# LKS_074DO.net
KiCad netlist of a schematic drawn in Altium Designer
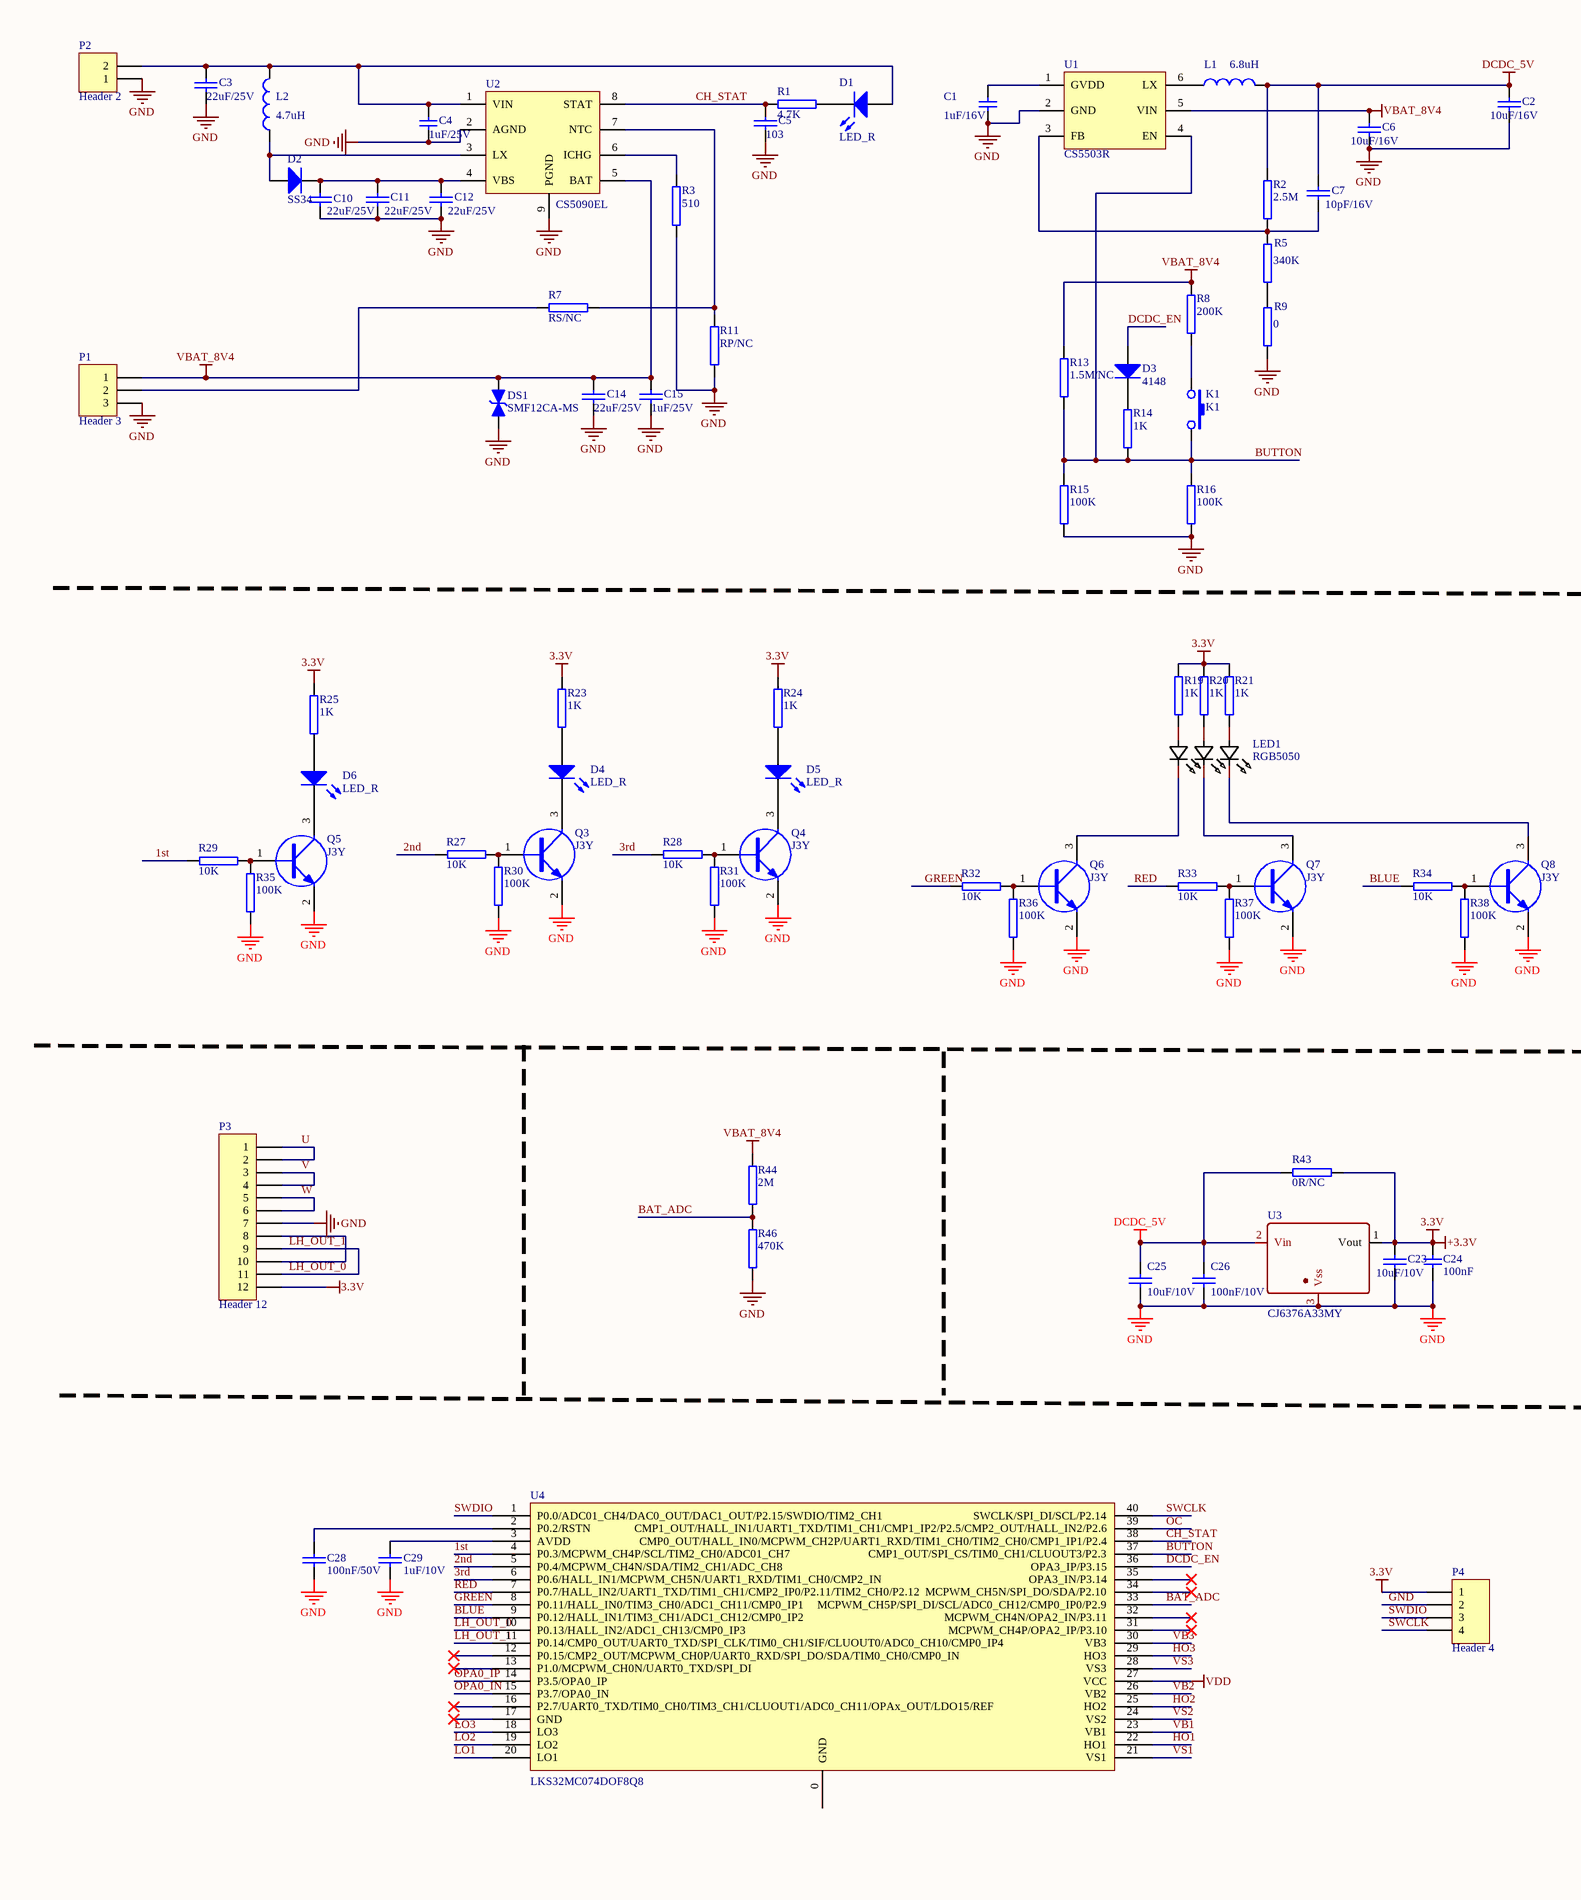
[diagram p0: LKS_074DO.SchDoc, left]
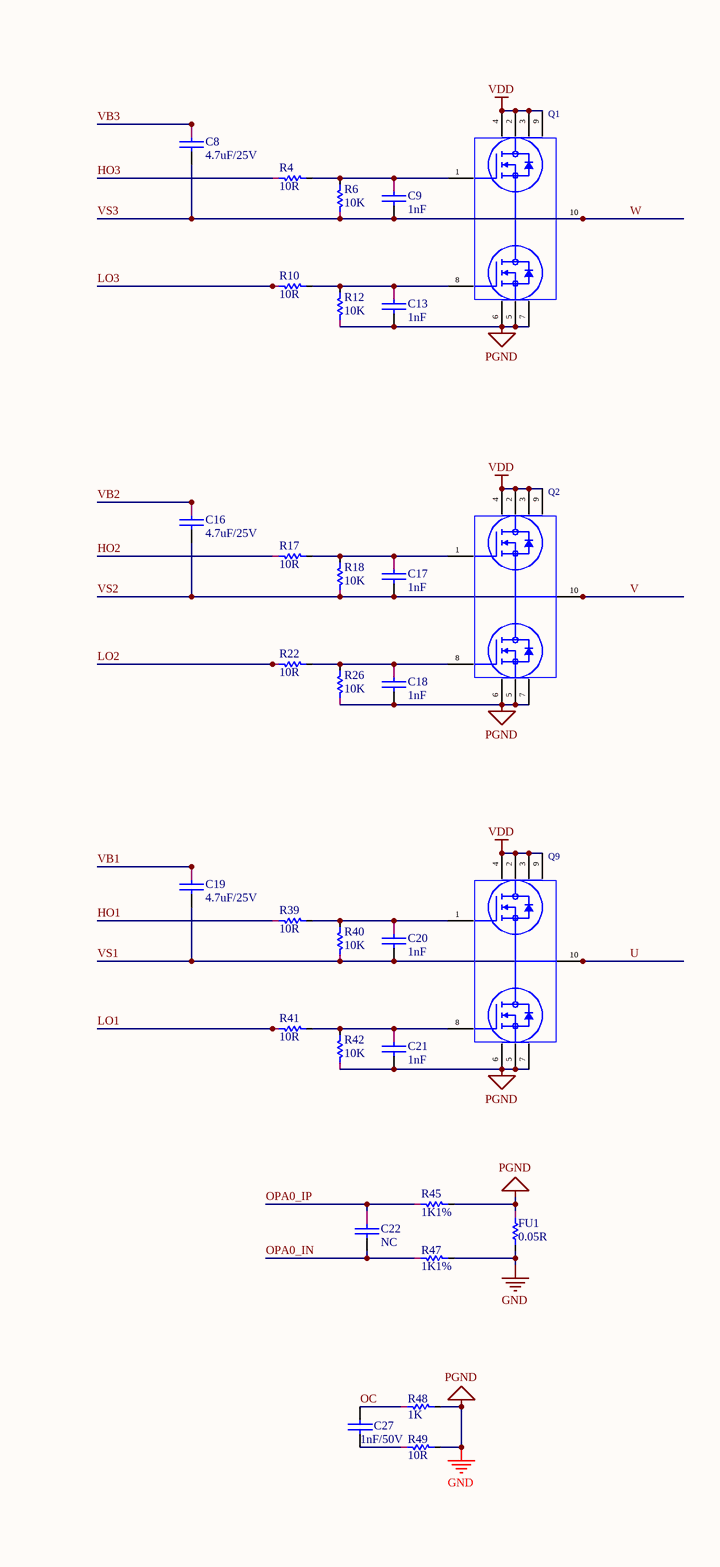
[diagram p1: LKS_074DO.SchDoc, right]

(export (version "E")
  (design (tool "Eeschema 10.0.6"))
  (components
    (comp (ref "C1") (value "1uF/16V") (footprint "C 0402_M") (libsource (lib "") (part "CAP_2")))
    (comp (ref "C2")
      (value "10uF/16V")
      (footprint "0805C")
      (description "Capacitor")
      (libsource (lib "*") (part "CAP"))
    )
    (comp (ref "C3")
      (value "22uF/25V")
      (footprint "0805C")
      (description "Capacitor")
      (libsource (lib "*") (part "CAP"))
    )
    (comp (ref "C4") (value "1uF/25V") (footprint "C 0402_M") (libsource (lib "") (part "CAP_2")))
    (comp (ref "C5")
      (value "103")
      (footprint "R 0402_M")
      (description "Capacitor")
      (libsource (lib "*") (part "CAP"))
    )
    (comp (ref "C6")
      (value "10uF/16V")
      (footprint "0805C")
      (description "Capacitor")
      (libsource (lib "*") (part "CAP"))
    )
    (comp (ref "C7")
      (value "10pF/16V")
      (footprint "C 0402_M")
      (description "Capacitor")
      (libsource (lib "*") (part "CAP"))
    )
    (comp (ref "C8")
      (value "4.7uF/25V")
      (footprint "C 0603_M")
      (description "Capacitor")
      (libsource (lib "") (part "CAP_1"))
    )
    (comp (ref "C9")
      (value "1nF")
      (footprint "C 0402_M")
      (description "Capacitor")
      (libsource (lib "") (part "CAP_1"))
    )
    (comp (ref "C10")
      (value "22uF/25V")
      (footprint "0805C")
      (description "Capacitor")
      (libsource (lib "*") (part "CAP"))
    )
    (comp (ref "C11")
      (value "22uF/25V")
      (footprint "0805C")
      (description "Capacitor")
      (libsource (lib "*") (part "CAP"))
    )
    (comp (ref "C12")
      (value "22uF/25V")
      (footprint "0805C")
      (description "Capacitor")
      (libsource (lib "*") (part "CAP"))
    )
    (comp (ref "C13")
      (value "1nF")
      (footprint "C 0402_M")
      (description "Capacitor")
      (libsource (lib "") (part "CAP_1"))
    )
    (comp (ref "C14")
      (value "22uF/25V")
      (footprint "0805C")
      (description "Capacitor")
      (libsource (lib "*") (part "CAP"))
    )
    (comp (ref "C15")
      (value "1uF/25V")
      (footprint "C 0603_M")
      (description "Capacitor")
      (libsource (lib "*") (part "CAP"))
    )
    (comp (ref "C16")
      (value "4.7uF/25V")
      (footprint "C 0603_M")
      (description "Capacitor")
      (libsource (lib "") (part "CAP_1"))
    )
    (comp (ref "C17")
      (value "1nF")
      (footprint "C 0402_M")
      (description "Capacitor")
      (libsource (lib "") (part "CAP_1"))
    )
    (comp (ref "C18")
      (value "1nF")
      (footprint "C 0402_M")
      (description "Capacitor")
      (libsource (lib "") (part "CAP_1"))
    )
    (comp (ref "C19")
      (value "4.7uF/25V")
      (footprint "C 0603_M")
      (description "Capacitor")
      (libsource (lib "") (part "CAP_1"))
    )
    (comp (ref "C20")
      (value "1nF")
      (footprint "C 0402_M")
      (description "Capacitor")
      (libsource (lib "") (part "CAP_1"))
    )
    (comp (ref "C21")
      (value "1nF")
      (footprint "C 0402_M")
      (description "Capacitor")
      (libsource (lib "") (part "CAP_1"))
    )
    (comp (ref "C22")
      (value "NC")
      (footprint "C 0402_M")
      (description "Capacitor")
      (libsource (lib "") (part "CAP_1"))
    )
    (comp (ref "C23")
      (value "10uF/10V")
      (footprint "0805C")
      (description "Capacitor")
      (libsource (lib "*") (part "CAP"))
    )
    (comp (ref "C24") (value "100nF") (footprint "C 0402_M") (libsource (lib "") (part "CAP_2")))
    (comp (ref "C25")
      (value "10uF/10V")
      (footprint "0805C")
      (description "Capacitor")
      (libsource (lib "*") (part "CAP"))
    )
    (comp (ref "C26")
      (value "100nF/10V")
      (footprint "C 0402_M")
      (description "Capacitor")
      (libsource (lib "*") (part "CAP"))
    )
    (comp (ref "C27")
      (value "1nF/50V")
      (footprint "C 0402_M")
      (description "Capacitor")
      (libsource (lib "*") (part "C"))
    )
    (comp (ref "C28")
      (value "100nF/50V")
      (footprint "C 0402_M")
      (description "Capacitor")
      (libsource (lib "*") (part "C"))
    )
    (comp (ref "C29")
      (value "1uF/10V")
      (footprint "0603")
      (description "Capacitor")
      (libsource (lib "*") (part "C"))
    )
    (comp (ref "D1") (value "LED_R") (footprint "SMDLED") (libsource (lib "PuXun1") (part "LED")))
    (comp (ref "D2")
      (value "SS34")
      (footprint "SMA")
      (description "Default Diode")
      (fields (field (name "PUBLISHER") "Altium Limited"))
      (libsource (lib "LKS034DO_Motor_0520_1") (part "Diode"))
    )
    (comp (ref "D3")
      (value "4148")
      (footprint "SOD-323")
      (description "Default Diode")
      (fields (field (name "PUBLISHER") "Altium Limited"))
      (libsource (lib "LKS034DO_Motor_0520_1") (part "Diode"))
    )
    (comp (ref "D4") (value "LED_R") (footprint "SMDLED") (libsource (lib "PuXun1") (part "LED")))
    (comp (ref "D5") (value "LED_R") (footprint "SMDLED") (libsource (lib "PuXun1") (part "LED")))
    (comp (ref "D6") (value "LED_R") (footprint "SMDLED") (libsource (lib "PuXun1") (part "LED")))
    (comp (ref "DS1")
      (value "SMF12CA-MS")
      (footprint "SOD-123F")
      (description "12V/19.9V")
      (libsource (lib "*") (part "DIODE-3"))
    )
    (comp (ref "FU1") (value "0.05R") (footprint "R 0805_M") (libsource (lib "*") (part "RAS")))
    (comp (ref "K1") (value "K1") (footprint "Button3x4x2") (libsource (lib "SCHLIB_NEW") (part "K1")))
    (comp (ref "L1")
      (value "6.8uH")
      (footprint "0630-10UH")
      (description "Inductor")
      (fields (field (name "PUBLISHER") "Altium Limited"))
      (libsource (lib "Miscellaneous Devices") (part "Inductor"))
    )
    (comp (ref "L2")
      (value "4.7uH")
      (footprint "0630-10UH")
      (description "Inductor")
      (fields (field (name "PUBLISHER") "Altium Limited"))
      (libsource (lib "Miscellaneous Devices") (part "Inductor"))
    )
    (comp (ref "LED1")
      (value "RGB5050")
      (footprint "RGB-5050")
      (libsource (lib "LKS034DO_Motor_0520_1") (part "RGB5050"))
    )
    (comp (ref "P1")
      (value "Header 3")
      (footprint "X9827WRS-3P")
      (description "Header, 3-Pin")
      (fields (field (name "PUBLISHER") "Altium Limited"))
      (libsource (lib "Miscellaneous Connectors") (part "Header 3"))
    )
    (comp (ref "P2")
      (value "Header 2")
      (footprint "CONN_SMD_2P_0.6")
      (description "Header, 2-Pin")
      (fields (field (name "PUBLISHER") "Altium Limited"))
      (libsource (lib "Miscellaneous Connectors") (part "Header 2"))
    )
    (comp (ref "P3")
      (value "Header 12")
      (footprint "SMD-12")
      (description "Header, 12-Pin")
      (fields (field (name "PUBLISHER") "Altium Limited"))
      (libsource (lib "Miscellaneous Connectors") (part "Header 12"))
    )
    (comp (ref "P4")
      (value "Header 4")
      (footprint "HDR1X4")
      (description "Header, 4-Pin")
      (fields (field (name "PUBLISHER") "Altium Limited"))
      (libsource (lib "Miscellaneous Connectors") (part "Header 4"))
    )
    (comp (ref "Q1") (value "CJBM3020") (footprint "DFN-3X3_8") (libsource (lib "*") (part "CJBM3020")))
    (comp (ref "Q2") (value "CJBM3020") (footprint "DFN-3X3_8") (libsource (lib "*") (part "CJBM3020")))
    (comp (ref "Q3")
      (value "J3Y")
      (footprint "SOT-23")
      (description "NPN Transistor")
      (libsource (lib "*") (part "NPN"))
    )
    (comp (ref "Q4")
      (value "J3Y")
      (footprint "SOT-23")
      (description "NPN Transistor")
      (libsource (lib "*") (part "NPN"))
    )
    (comp (ref "Q5")
      (value "J3Y")
      (footprint "SOT-23")
      (description "NPN Transistor")
      (libsource (lib "*") (part "NPN"))
    )
    (comp (ref "Q6")
      (value "J3Y")
      (footprint "SOT-23")
      (description "NPN Transistor")
      (libsource (lib "*") (part "NPN"))
    )
    (comp (ref "Q7")
      (value "J3Y")
      (footprint "SOT-23")
      (description "NPN Transistor")
      (libsource (lib "*") (part "NPN"))
    )
    (comp (ref "Q8")
      (value "J3Y")
      (footprint "SOT-23")
      (description "NPN Transistor")
      (libsource (lib "*") (part "NPN"))
    )
    (comp (ref "Q9") (value "CJBM3020") (footprint "DFN-3X3_8") (libsource (lib "*") (part "CJBM3020")))
    (comp (ref "R1") (value "4.7K") (footprint "C 0402_M") (libsource (lib "*") (part "RES2_S")))
    (comp (ref "R2") (value "2.5M") (footprint "C 0402_M") (libsource (lib "*") (part "RES2_S")))
    (comp (ref "R3") (value "510") (footprint "R 0402_M") (libsource (lib "*") (part "RES2_S")))
    (comp (ref "R4") (value "10R") (footprint "R 0402_M") (libsource (lib "*") (part "RAS")))
    (comp (ref "R5") (value "340K") (footprint "C 0402_M") (libsource (lib "*") (part "RES2_S")))
    (comp (ref "R6") (value "10K") (footprint "R 0402_M") (libsource (lib "*") (part "RAS")))
    (comp (ref "R7") (value "RS/NC") (footprint "R 0402_M") (libsource (lib "*") (part "RES2_S")))
    (comp (ref "R8") (value "200K") (footprint "C 0402_M") (libsource (lib "*") (part "RES2_S")))
    (comp (ref "R9") (value "0") (footprint "C 0402_M") (libsource (lib "*") (part "RES2_S")))
    (comp (ref "R10") (value "10R") (footprint "R 0402_M") (libsource (lib "*") (part "RAS")))
    (comp (ref "R11") (value "RP/NC") (footprint "R 0402_M") (libsource (lib "*") (part "RES2_S")))
    (comp (ref "R12") (value "10K") (footprint "R 0402_M") (libsource (lib "*") (part "RAS")))
    (comp (ref "R13") (value "1.5M/NC") (footprint "C 0402_M") (libsource (lib "*") (part "RES2_S")))
    (comp (ref "R14") (value "1K") (footprint "C 0402_M") (libsource (lib "*") (part "RES2_S")))
    (comp (ref "R15") (value "100K") (footprint "C 0402_M") (libsource (lib "*") (part "RES2_S")))
    (comp (ref "R16") (value "100K") (footprint "C 0402_M") (libsource (lib "*") (part "RES2_S")))
    (comp (ref "R17") (value "10R") (footprint "R 0402_M") (libsource (lib "*") (part "RAS")))
    (comp (ref "R18") (value "10K") (footprint "R 0402_M") (libsource (lib "*") (part "RAS")))
    (comp (ref "R19") (value "1K") (footprint "C 0402_M") (libsource (lib "*") (part "RES2_S")))
    (comp (ref "R20") (value "1K") (footprint "C 0402_M") (libsource (lib "*") (part "RES2_S")))
    (comp (ref "R21") (value "1K") (footprint "C 0402_M") (libsource (lib "*") (part "RES2_S")))
    (comp (ref "R22") (value "10R") (footprint "R 0402_M") (libsource (lib "*") (part "RAS")))
    (comp (ref "R23") (value "1K") (footprint "C 0402_M") (libsource (lib "*") (part "RES2_S")))
    (comp (ref "R24") (value "1K") (footprint "C 0402_M") (libsource (lib "*") (part "RES2_S")))
    (comp (ref "R25") (value "1K") (footprint "C 0402_M") (libsource (lib "*") (part "RES2_S")))
    (comp (ref "R26") (value "10K") (footprint "R 0402_M") (libsource (lib "*") (part "RAS")))
    (comp (ref "R27") (value "10K") (footprint "C 0402_M") (libsource (lib "*") (part "RES2_S")))
    (comp (ref "R28") (value "10K") (footprint "C 0402_M") (libsource (lib "*") (part "RES2_S")))
    (comp (ref "R29") (value "10K") (footprint "C 0402_M") (libsource (lib "*") (part "RES2_S")))
    (comp (ref "R30") (value "100K") (footprint "C 0402_M") (libsource (lib "*") (part "RES2_S")))
    (comp (ref "R31") (value "100K") (footprint "C 0402_M") (libsource (lib "*") (part "RES2_S")))
    (comp (ref "R32") (value "10K") (footprint "C 0402_M") (libsource (lib "*") (part "RES2_S")))
    (comp (ref "R33") (value "10K") (footprint "C 0402_M") (libsource (lib "*") (part "RES2_S")))
    (comp (ref "R34") (value "10K") (footprint "C 0402_M") (libsource (lib "*") (part "RES2_S")))
    (comp (ref "R35") (value "100K") (footprint "C 0402_M") (libsource (lib "*") (part "RES2_S")))
    (comp (ref "R36") (value "100K") (footprint "C 0402_M") (libsource (lib "*") (part "RES2_S")))
    (comp (ref "R37") (value "100K") (footprint "C 0402_M") (libsource (lib "*") (part "RES2_S")))
    (comp (ref "R38") (value "100K") (footprint "C 0402_M") (libsource (lib "*") (part "RES2_S")))
    (comp (ref "R39") (value "10R") (footprint "R 0402_M") (libsource (lib "*") (part "RAS")))
    (comp (ref "R40") (value "10K") (footprint "R 0402_M") (libsource (lib "*") (part "RAS")))
    (comp (ref "R41") (value "10R") (footprint "R 0402_M") (libsource (lib "*") (part "RAS")))
    (comp (ref "R42") (value "10K") (footprint "R 0402_M") (libsource (lib "*") (part "RAS")))
    (comp (ref "R43") (value "0R/NC") (footprint "R 0805_M") (libsource (lib "*") (part "RES2_S")))
    (comp (ref "R44") (value "2M") (footprint "C 0402_M") (libsource (lib "*") (part "RES2_S")))
    (comp (ref "R45") (value "1K1%") (footprint "R 0402_M") (libsource (lib "*") (part "RAS")))
    (comp (ref "R46") (value "470K") (footprint "C 0402_M") (libsource (lib "*") (part "RES2_S")))
    (comp (ref "R47") (value "1K1%") (footprint "R 0402_M") (libsource (lib "*") (part "RAS")))
    (comp (ref "R48") (value "1K") (footprint "R 0402_M") (libsource (lib "*") (part "RAS")))
    (comp (ref "R49") (value "10R") (footprint "R 0402_M") (libsource (lib "*") (part "RAS")))
    (comp (ref "U1")
      (value "CS5503R")
      (footprint "SOT23-6L")
      (libsource (lib "LKS034DO_Motor_0520_1") (part "CS5503R"))
    )
    (comp (ref "U2")
      (value "CS5090EL")
      (footprint "DFN2X2_8_0.5")
      (libsource (lib "LKS034DO_Motor_0520_1") (part "CS5090EL"))
    )
    (comp (ref "U3")
      (value "CJ6376A33MY")
      (footprint "SOT-23")
      (libsource (lib "LKS034DO_Motor_0520_1") (part "78L15"))
    )
    (comp (ref "U4")
      (value "LKS32MC074DOF8Q8")
      (footprint "QFN40")
      (description "芯片")
      (libsource (lib "Q_LINKO_V1.0") (part "LKS32MC074DF8Q8"))
    )
  )
  (nets
    (net (code "1") (name "+3.3V") (class "Default")
      (node (ref "C23") (pin "2") (pinfunction "2_2") (pintype "passive"))
      (node (ref "C24") (pin "1") (pinfunction "1_1") (pintype "passive"))
      (node (ref "P3") (pin "12") (pinfunction "12_12") (pintype "passive"))
      (node (ref "P4") (pin "1") (pinfunction "1_1") (pintype "passive"))
      (node (ref "R19") (pin "2") (pinfunction "2_2") (pintype "passive"))
      (node (ref "R20") (pin "2") (pinfunction "2_2") (pintype "passive"))
      (node (ref "R21") (pin "2") (pinfunction "2_2") (pintype "passive"))
      (node (ref "R23") (pin "2") (pinfunction "2_2") (pintype "passive"))
      (node (ref "R24") (pin "2") (pinfunction "2_2") (pintype "passive"))
      (node (ref "R25") (pin "2") (pinfunction "2_2") (pintype "passive"))
      (node (ref "R43") (pin "2") (pinfunction "2_2") (pintype "passive"))
      (node (ref "U3") (pin "1") (pinfunction "Vout_1") (pintype "passive"))
    )
    (net (code "2") (name "/1st") (class "Default")
      (node (ref "R29") (pin "2") (pinfunction "2_2") (pintype "passive"))
      (node (ref "U4") (pin "4") (pinfunction "P0.3/MCPWM_CH4P/SCL/TIM2_CH0/ADC01_CH7_4") (pintype "passive"))
    )
    (net (code "3") (name "/2nd") (class "Default")
      (node (ref "R27") (pin "2") (pinfunction "2_2") (pintype "passive"))
      (node (ref "U4") (pin "5") (pinfunction "P0.4/MCPWM_CH4N/SDA/TIM2_CH1/ADC_CH8_5") (pintype "passive"))
    )
    (net (code "4") (name "/3rd") (class "Default")
      (node (ref "R28") (pin "2") (pinfunction "2_2") (pintype "passive"))
      (node (ref "U4") (pin "6") (pinfunction "P0.6/HALL_IN1/MCPWM_CH5N/UART1_RXD/TIM1_CH0/CMP2_IN_6") (pintype "passive"))
    )
    (net (code "5") (name "/BAT_ADC") (class "Default")
      (node (ref "R44") (pin "2") (pinfunction "2_2") (pintype "passive"))
      (node (ref "R46") (pin "1") (pinfunction "1_1") (pintype "passive"))
      (node (ref "U4") (pin "33") (pinfunction "MCPWM_CH5P/SPI_DI/SCL/ADC0_CH12/CMP0_IP0/P2.9_33") (pintype "passive"))
    )
    (net (code "6") (name "/BLUE") (class "Default")
      (node (ref "R34") (pin "2") (pinfunction "2_2") (pintype "passive"))
      (node (ref "U4") (pin "9") (pinfunction "P0.12/HALL_IN1/TIM3_CH1/ADC1_CH12/CMP0_IP2_9") (pintype "passive"))
    )
    (net (code "7") (name "/BUTTON") (class "Default")
      (node (ref "K1") (pin "2") (pintype "passive"))
      (node (ref "R13") (pin "2") (pinfunction "2_2") (pintype "passive"))
      (node (ref "R14") (pin "2") (pinfunction "2_2") (pintype "passive"))
      (node (ref "R15") (pin "2") (pinfunction "2_2") (pintype "passive"))
      (node (ref "R16") (pin "1") (pinfunction "1_1") (pintype "passive"))
      (node (ref "U1") (pin "4") (pinfunction "EN_4") (pintype "passive"))
      (node (ref "U4") (pin "37") (pinfunction "CMP1_OUT/SPI_CS/TIM0_CH1/CLUOUT3/P2.3_37") (pintype "passive"))
    )
    (net (code "8") (name "/CH_STAT") (class "Default")
      (node (ref "C5") (pin "2") (pinfunction "2_2") (pintype "passive"))
      (node (ref "R1") (pin "1") (pinfunction "1_1") (pintype "passive"))
      (node (ref "U2") (pin "8") (pinfunction "STAT_8") (pintype "passive"))
      (node (ref "U4") (pin "38") (pinfunction "CMP0_OUT/HALL_IN0/MCPWM_CH2P/UART1_RXD/TIM1_CH0/TIM2_CH0/CMP1_IP1/P2.4_38") (pintype "passive"))
    )
    (net (code "9") (name "/DCDC_EN") (class "Default")
      (node (ref "D3") (pin "1") (pinfunction "A_1") (pintype "passive"))
      (node (ref "U4") (pin "36") (pinfunction "OPA3_IP/P3.15_36") (pintype "passive"))
    )
    (net (code "10") (name "/GREEN") (class "Default")
      (node (ref "R32") (pin "2") (pinfunction "2_2") (pintype "passive"))
      (node (ref "U4") (pin "8") (pinfunction "P0.11/HALL_IN0/TIM3_CH0/ADC1_CH11/CMP0_IP1_8") (pintype "passive"))
    )
    (net (code "11") (name "/HO1") (class "Default")
      (node (ref "R39") (pin "2") (pinfunction "2_2") (pintype "passive"))
      (node (ref "U4") (pin "22") (pinfunction "HO1_22") (pintype "passive"))
    )
    (net (code "12") (name "/HO2") (class "Default")
      (node (ref "R17") (pin "2") (pinfunction "2_2") (pintype "passive"))
      (node (ref "U4") (pin "25") (pinfunction "HO2_25") (pintype "passive"))
    )
    (net (code "13") (name "/HO3") (class "Default")
      (node (ref "R4") (pin "2") (pinfunction "2_2") (pintype "passive"))
      (node (ref "U4") (pin "29") (pinfunction "HO3_29") (pintype "passive"))
    )
    (net (code "14") (name "/LH_OUT_0") (class "Default")
      (node (ref "P3") (pin "11") (pinfunction "11_11") (pintype "passive"))
      (node (ref "P3") (pin "9") (pinfunction "9_9") (pintype "passive"))
      (node (ref "U4") (pin "10") (pinfunction "P0.13/HALL_IN2/ADC1_CH13/CMP0_IP3_10") (pintype "passive"))
      (node (ref "U4") (pin "11") (pinfunction "P0.14/CMP0_OUT/UART0_TXD/SPI_CLK/TIM0_CH1/SIF/CLUOUT0/ADC0_CH10/CMP0_IP4_11") (pintype "passive"))
    )
    (net (code "15") (name "/LO1") (class "Default")
      (node (ref "R41") (pin "2") (pinfunction "2_2") (pintype "passive"))
      (node (ref "U4") (pin "20") (pinfunction "LO1_20") (pintype "passive"))
    )
    (net (code "16") (name "/LO2") (class "Default")
      (node (ref "R22") (pin "2") (pinfunction "2_2") (pintype "passive"))
      (node (ref "U4") (pin "19") (pinfunction "LO2_19") (pintype "passive"))
    )
    (net (code "17") (name "/LO3") (class "Default")
      (node (ref "R10") (pin "2") (pinfunction "2_2") (pintype "passive"))
      (node (ref "U4") (pin "18") (pinfunction "LO3_18") (pintype "passive"))
    )
    (net (code "18") (name "/OC") (class "Default")
      (node (ref "C27") (pin "2") (pinfunction "2_2") (pintype "passive"))
      (node (ref "R48") (pin "2") (pinfunction "2_2") (pintype "passive"))
      (node (ref "U4") (pin "39") (pinfunction "CMP1_OUT/HALL_IN1/UART1_TXD/TIM1_CH1/CMP1_IP2/P2.5/CMP2_OUT/HALL_IN2/P2.6_39") (pintype "passive"))
    )
    (net (code "19") (name "/OPA0_IN") (class "Default")
      (node (ref "C22") (pin "1") (pinfunction "1_1") (pintype "passive"))
      (node (ref "R47") (pin "2") (pinfunction "2_2") (pintype "passive"))
      (node (ref "U4") (pin "15") (pinfunction "P3.7/OPA0_IN_15") (pintype "passive"))
    )
    (net (code "20") (name "/OPA0_IP") (class "Default")
      (node (ref "C22") (pin "2") (pinfunction "2_2") (pintype "passive"))
      (node (ref "R45") (pin "2") (pinfunction "2_2") (pintype "passive"))
      (node (ref "U4") (pin "14") (pinfunction "P3.5/OPA0_IP_14") (pintype "passive"))
    )
    (net (code "21") (name "/RED") (class "Default")
      (node (ref "R33") (pin "2") (pinfunction "2_2") (pintype "passive"))
      (node (ref "U4") (pin "7") (pinfunction "P0.7/HALL_IN2/UART1_TXD/TIM1_CH1/CMP2_IP0/P2.11/TIM2_CH0/P2.12_7") (pintype "passive"))
    )
    (net (code "22") (name "/SWCLK") (class "Default")
      (node (ref "P4") (pin "4") (pinfunction "4_4") (pintype "passive"))
      (node (ref "U4") (pin "40") (pinfunction "SWCLK/SPI_DI/SCL/P2.14_40") (pintype "passive"))
    )
    (net (code "23") (name "/SWDIO") (class "Default")
      (node (ref "P4") (pin "3") (pinfunction "3_3") (pintype "passive"))
      (node (ref "U4") (pin "1") (pinfunction "P0.0/ADC01_CH4/DAC0_OUT/DAC1_OUT/P2.15/SWDIO/TIM2_CH1_1") (pintype "passive"))
    )
    (net (code "24") (name "/U") (class "Default")
      (node (ref "C19") (pin "1") (pinfunction "1_1") (pintype "passive"))
      (node (ref "C20") (pin "1") (pinfunction "1_1") (pintype "passive"))
      (node (ref "P3") (pin "1") (pinfunction "1_1") (pintype "passive"))
      (node (ref "P3") (pin "2") (pinfunction "2_2") (pintype "passive"))
      (node (ref "Q9") (pin "10") (pinfunction "S1/D2_10") (pintype "passive"))
      (node (ref "R40") (pin "2") (pinfunction "2_2") (pintype "passive"))
      (node (ref "U4") (pin "21") (pinfunction "VS1_21") (pintype "passive"))
    )
    (net (code "25") (name "/V") (class "Default")
      (node (ref "C16") (pin "1") (pinfunction "1_1") (pintype "passive"))
      (node (ref "C17") (pin "1") (pinfunction "1_1") (pintype "passive"))
      (node (ref "P3") (pin "3") (pinfunction "3_3") (pintype "passive"))
      (node (ref "P3") (pin "4") (pinfunction "4_4") (pintype "passive"))
      (node (ref "Q2") (pin "10") (pinfunction "S1/D2_10") (pintype "passive"))
      (node (ref "R18") (pin "2") (pinfunction "2_2") (pintype "passive"))
      (node (ref "U4") (pin "24") (pinfunction "VS2_24") (pintype "passive"))
    )
    (net (code "26") (name "/VB1") (class "Default")
      (node (ref "C19") (pin "2") (pinfunction "2_2") (pintype "passive"))
      (node (ref "U4") (pin "23") (pinfunction "VB1_23") (pintype "passive"))
    )
    (net (code "27") (name "/VB2") (class "Default")
      (node (ref "C16") (pin "2") (pinfunction "2_2") (pintype "passive"))
      (node (ref "U4") (pin "26") (pinfunction "VB2_26") (pintype "passive"))
    )
    (net (code "28") (name "/VB3") (class "Default")
      (node (ref "C8") (pin "2") (pinfunction "2_2") (pintype "passive"))
      (node (ref "U4") (pin "30") (pinfunction "VB3_30") (pintype "passive"))
    )
    (net (code "29") (name "/VS3") (class "Default")
      (node (ref "C8") (pin "1") (pinfunction "1_1") (pintype "passive"))
      (node (ref "C9") (pin "1") (pinfunction "1_1") (pintype "passive"))
      (node (ref "P3") (pin "5") (pinfunction "5_5") (pintype "passive"))
      (node (ref "P3") (pin "6") (pinfunction "6_6") (pintype "passive"))
      (node (ref "Q1") (pin "10") (pinfunction "S1/D2_10") (pintype "passive"))
      (node (ref "R6") (pin "2") (pinfunction "2_2") (pintype "passive"))
      (node (ref "U4") (pin "28") (pinfunction "VS3_28") (pintype "passive"))
    )
    (net (code "30") (name "DCDC_5V") (class "Default")
      (node (ref "C2") (pin "2") (pinfunction "2_2") (pintype "passive"))
      (node (ref "C25") (pin "2") (pinfunction "2_2") (pintype "passive"))
      (node (ref "C26") (pin "1") (pinfunction "1_1") (pintype "passive"))
      (node (ref "C7") (pin "2") (pinfunction "2_2") (pintype "passive"))
      (node (ref "L1") (pin "2") (pinfunction "2_2") (pintype "passive"))
      (node (ref "R2") (pin "1") (pinfunction "1_1") (pintype "passive"))
      (node (ref "R43") (pin "1") (pinfunction "1_1") (pintype "passive"))
      (node (ref "U3") (pin "2") (pinfunction "Vin_2") (pintype "passive"))
    )
    (net (code "31") (name "GND") (class "Default")
      (node (ref "C1") (pin "1") (pinfunction "1_1") (pintype "passive"))
      (node (ref "C10") (pin "1") (pinfunction "1_1") (pintype "passive"))
      (node (ref "C11") (pin "1") (pinfunction "1_1") (pintype "passive"))
      (node (ref "C12") (pin "1") (pinfunction "1_1") (pintype "passive"))
      (node (ref "C13") (pin "1") (pinfunction "1_1") (pintype "passive"))
      (node (ref "C14") (pin "1") (pinfunction "1_1") (pintype "passive"))
      (node (ref "C15") (pin "1") (pinfunction "1_1") (pintype "passive"))
      (node (ref "C18") (pin "1") (pinfunction "1_1") (pintype "passive"))
      (node (ref "C2") (pin "1") (pinfunction "1_1") (pintype "passive"))
      (node (ref "C21") (pin "1") (pinfunction "1_1") (pintype "passive"))
      (node (ref "C23") (pin "1") (pinfunction "1_1") (pintype "passive"))
      (node (ref "C24") (pin "2") (pinfunction "2_2") (pintype "passive"))
      (node (ref "C25") (pin "1") (pinfunction "1_1") (pintype "passive"))
      (node (ref "C26") (pin "2") (pinfunction "2_2") (pintype "passive"))
      (node (ref "C28") (pin "2") (pinfunction "2_2") (pintype "passive"))
      (node (ref "C29") (pin "1") (pinfunction "1_1") (pintype "passive"))
      (node (ref "C3") (pin "1") (pinfunction "1_1") (pintype "passive"))
      (node (ref "C4") (pin "2") (pinfunction "2_2") (pintype "passive"))
      (node (ref "C5") (pin "1") (pinfunction "1_1") (pintype "passive"))
      (node (ref "C6") (pin "1") (pinfunction "1_1") (pintype "passive"))
      (node (ref "DS1") (pin "2") (pinfunction "K_2") (pintype "passive"))
      (node (ref "FU1") (pin "1") (pinfunction "1_1") (pintype "passive"))
      (node (ref "FU1") (pin "2") (pinfunction "2_2") (pintype "passive"))
      (node (ref "P1") (pin "3") (pinfunction "3_3") (pintype "passive"))
      (node (ref "P2") (pin "1") (pinfunction "1_1") (pintype "passive"))
      (node (ref "P3") (pin "7") (pinfunction "7_7") (pintype "passive"))
      (node (ref "P4") (pin "2") (pinfunction "2_2") (pintype "passive"))
      (node (ref "Q1") (pin "5") (pinfunction "S2_5") (pintype "passive"))
      (node (ref "Q1") (pin "6") (pinfunction "S2_6") (pintype "passive"))
      (node (ref "Q1") (pin "7") (pinfunction "S2_7") (pintype "passive"))
      (node (ref "Q2") (pin "5") (pinfunction "S2_5") (pintype "passive"))
      (node (ref "Q2") (pin "6") (pinfunction "S2_6") (pintype "passive"))
      (node (ref "Q2") (pin "7") (pinfunction "S2_7") (pintype "passive"))
      (node (ref "Q3") (pin "2") (pinfunction "E_2") (pintype "passive"))
      (node (ref "Q4") (pin "2") (pinfunction "E_2") (pintype "passive"))
      (node (ref "Q5") (pin "2") (pinfunction "E_2") (pintype "passive"))
      (node (ref "Q6") (pin "2") (pinfunction "E_2") (pintype "passive"))
      (node (ref "Q7") (pin "2") (pinfunction "E_2") (pintype "passive"))
      (node (ref "Q8") (pin "2") (pinfunction "E_2") (pintype "passive"))
      (node (ref "Q9") (pin "5") (pinfunction "S2_5") (pintype "passive"))
      (node (ref "Q9") (pin "6") (pinfunction "S2_6") (pintype "passive"))
      (node (ref "Q9") (pin "7") (pinfunction "S2_7") (pintype "passive"))
      (node (ref "R11") (pin "2") (pinfunction "2_2") (pintype "passive"))
      (node (ref "R12") (pin "2") (pinfunction "2_2") (pintype "passive"))
      (node (ref "R15") (pin "1") (pinfunction "1_1") (pintype "passive"))
      (node (ref "R16") (pin "2") (pinfunction "2_2") (pintype "passive"))
      (node (ref "R26") (pin "2") (pinfunction "2_2") (pintype "passive"))
      (node (ref "R3") (pin "2") (pinfunction "2_2") (pintype "passive"))
      (node (ref "R30") (pin "2") (pinfunction "2_2") (pintype "passive"))
      (node (ref "R31") (pin "2") (pinfunction "2_2") (pintype "passive"))
      (node (ref "R35") (pin "2") (pinfunction "2_2") (pintype "passive"))
      (node (ref "R36") (pin "2") (pinfunction "2_2") (pintype "passive"))
      (node (ref "R37") (pin "2") (pinfunction "2_2") (pintype "passive"))
      (node (ref "R38") (pin "2") (pinfunction "2_2") (pintype "passive"))
      (node (ref "R42") (pin "2") (pinfunction "2_2") (pintype "passive"))
      (node (ref "R45") (pin "1") (pinfunction "1_1") (pintype "passive"))
      (node (ref "R46") (pin "2") (pinfunction "2_2") (pintype "passive"))
      (node (ref "R47") (pin "1") (pinfunction "1_1") (pintype "passive"))
      (node (ref "R48") (pin "1") (pinfunction "1_1") (pintype "passive"))
      (node (ref "R49") (pin "1") (pinfunction "1_1") (pintype "passive"))
      (node (ref "R9") (pin "2") (pinfunction "2_2") (pintype "passive"))
      (node (ref "U1") (pin "2") (pinfunction "GND_2") (pintype "passive"))
      (node (ref "U2") (pin "2") (pinfunction "AGND_2") (pintype "passive"))
      (node (ref "U2") (pin "9") (pinfunction "PGND_9") (pintype "passive"))
      (node (ref "U3") (pin "3") (pinfunction "Vss_3") (pintype "passive"))
    )
    (net (code "32") (name "Net-(C27-Pad1)") (class "Default")
      (node (ref "C27") (pin "1") (pinfunction "1_1") (pintype "passive"))
      (node (ref "R49") (pin "2") (pinfunction "2_2") (pintype "passive"))
    )
    (net (code "33") (name "Net-(D1-A)") (class "Default")
      (node (ref "C3") (pin "2") (pinfunction "2_2") (pintype "passive"))
      (node (ref "C4") (pin "1") (pinfunction "1_1") (pintype "passive"))
      (node (ref "D1") (pin "1") (pinfunction "A_1") (pintype "passive"))
      (node (ref "L2") (pin "2") (pinfunction "2_2") (pintype "passive"))
      (node (ref "P2") (pin "2") (pinfunction "2_2") (pintype "passive"))
      (node (ref "U2") (pin "1") (pinfunction "VIN_1") (pintype "passive"))
    )
    (net (code "34") (name "Net-(D1-K)") (class "Default")
      (node (ref "D1") (pin "2") (pinfunction "K_2") (pintype "passive"))
      (node (ref "R1") (pin "2") (pinfunction "2_2") (pintype "passive"))
    )
    (net (code "35") (name "Net-(D2-A)") (class "Default")
      (node (ref "D2") (pin "1") (pinfunction "A_1") (pintype "passive"))
      (node (ref "L2") (pin "1") (pinfunction "1_1") (pintype "passive"))
      (node (ref "U2") (pin "3") (pinfunction "LX_3") (pintype "passive"))
    )
    (net (code "36") (name "Net-(D2-K)") (class "Default")
      (node (ref "C10") (pin "2") (pinfunction "2_2") (pintype "passive"))
      (node (ref "C11") (pin "2") (pinfunction "2_2") (pintype "passive"))
      (node (ref "C12") (pin "2") (pinfunction "2_2") (pintype "passive"))
      (node (ref "D2") (pin "2") (pinfunction "K_2") (pintype "passive"))
      (node (ref "U2") (pin "4") (pinfunction "VBS_4") (pintype "passive"))
    )
    (net (code "37") (name "Net-(D3-K)") (class "Default")
      (node (ref "D3") (pin "2") (pinfunction "K_2") (pintype "passive"))
      (node (ref "R14") (pin "1") (pinfunction "1_1") (pintype "passive"))
    )
    (net (code "38") (name "Net-(D4-A)") (class "Default")
      (node (ref "D4") (pin "1") (pinfunction "A_1") (pintype "passive"))
      (node (ref "R23") (pin "1") (pinfunction "1_1") (pintype "passive"))
    )
    (net (code "39") (name "Net-(D4-K)") (class "Default")
      (node (ref "D4") (pin "2") (pinfunction "K_2") (pintype "passive"))
      (node (ref "Q3") (pin "3") (pinfunction "C_3") (pintype "passive"))
    )
    (net (code "40") (name "Net-(D5-A)") (class "Default")
      (node (ref "D5") (pin "1") (pinfunction "A_1") (pintype "passive"))
      (node (ref "R24") (pin "1") (pinfunction "1_1") (pintype "passive"))
    )
    (net (code "41") (name "Net-(D5-K)") (class "Default")
      (node (ref "D5") (pin "2") (pinfunction "K_2") (pintype "passive"))
      (node (ref "Q4") (pin "3") (pinfunction "C_3") (pintype "passive"))
    )
    (net (code "42") (name "Net-(D6-A)") (class "Default")
      (node (ref "D6") (pin "1") (pinfunction "A_1") (pintype "passive"))
      (node (ref "R25") (pin "1") (pinfunction "1_1") (pintype "passive"))
    )
    (net (code "43") (name "Net-(D6-K)") (class "Default")
      (node (ref "D6") (pin "2") (pinfunction "K_2") (pintype "passive"))
      (node (ref "Q5") (pin "3") (pinfunction "C_3") (pintype "passive"))
    )
    (net (code "44") (name "Net-(K1-Pad1)") (class "Default")
      (node (ref "K1") (pin "1") (pintype "passive"))
      (node (ref "R8") (pin "1") (pinfunction "1_1") (pintype "passive"))
    )
    (net (code "45") (name "Net-(LED1-+-Pad1)") (class "Default")
      (node (ref "LED1") (pin "1") (pinfunction "+_1") (pintype "passive"))
      (node (ref "R21") (pin "1") (pinfunction "1_1") (pintype "passive"))
    )
    (net (code "46") (name "Net-(LED1-+-Pad2)") (class "Default")
      (node (ref "LED1") (pin "2") (pinfunction "+_2") (pintype "passive"))
      (node (ref "R20") (pin "1") (pinfunction "1_1") (pintype "passive"))
    )
    (net (code "47") (name "Net-(LED1-+-Pad3)") (class "Default")
      (node (ref "LED1") (pin "3") (pinfunction "+_3") (pintype "passive"))
      (node (ref "R19") (pin "1") (pinfunction "1_1") (pintype "passive"))
    )
    (net (code "48") (name "Net-(P1-Pad2)") (class "Default")
      (node (ref "P1") (pin "2") (pinfunction "2_2") (pintype "passive"))
      (node (ref "R7") (pin "1") (pinfunction "1_1") (pintype "passive"))
    )
    (net (code "49") (name "Net-(P3-Pad10)") (class "Default")
      (node (ref "P3") (pin "10") (pinfunction "10_10") (pintype "passive"))
      (node (ref "P3") (pin "8") (pinfunction "8_8") (pintype "passive"))
    )
    (net (code "50") (name "Net-(Q1-G1)") (class "Default")
      (node (ref "C9") (pin "2") (pinfunction "2_2") (pintype "passive"))
      (node (ref "Q1") (pin "1") (pinfunction "G1_1") (pintype "passive"))
      (node (ref "R4") (pin "1") (pinfunction "1_1") (pintype "passive"))
      (node (ref "R6") (pin "1") (pinfunction "1_1") (pintype "passive"))
    )
    (net (code "51") (name "Net-(Q1-G2)") (class "Default")
      (node (ref "C13") (pin "2") (pinfunction "2_2") (pintype "passive"))
      (node (ref "Q1") (pin "8") (pinfunction "G2_8") (pintype "passive"))
      (node (ref "R10") (pin "1") (pinfunction "1_1") (pintype "passive"))
      (node (ref "R12") (pin "1") (pinfunction "1_1") (pintype "passive"))
    )
    (net (code "52") (name "Net-(Q2-G1)") (class "Default")
      (node (ref "C17") (pin "2") (pinfunction "2_2") (pintype "passive"))
      (node (ref "Q2") (pin "1") (pinfunction "G1_1") (pintype "passive"))
      (node (ref "R17") (pin "1") (pinfunction "1_1") (pintype "passive"))
      (node (ref "R18") (pin "1") (pinfunction "1_1") (pintype "passive"))
    )
    (net (code "53") (name "Net-(Q2-G2)") (class "Default")
      (node (ref "C18") (pin "2") (pinfunction "2_2") (pintype "passive"))
      (node (ref "Q2") (pin "8") (pinfunction "G2_8") (pintype "passive"))
      (node (ref "R22") (pin "1") (pinfunction "1_1") (pintype "passive"))
      (node (ref "R26") (pin "1") (pinfunction "1_1") (pintype "passive"))
    )
    (net (code "54") (name "Net-(Q3-B)") (class "Default")
      (node (ref "Q3") (pin "1") (pinfunction "B_1") (pintype "passive"))
      (node (ref "R27") (pin "1") (pinfunction "1_1") (pintype "passive"))
      (node (ref "R30") (pin "1") (pinfunction "1_1") (pintype "passive"))
    )
    (net (code "55") (name "Net-(Q4-B)") (class "Default")
      (node (ref "Q4") (pin "1") (pinfunction "B_1") (pintype "passive"))
      (node (ref "R28") (pin "1") (pinfunction "1_1") (pintype "passive"))
      (node (ref "R31") (pin "1") (pinfunction "1_1") (pintype "passive"))
    )
    (net (code "56") (name "Net-(Q5-B)") (class "Default")
      (node (ref "Q5") (pin "1") (pinfunction "B_1") (pintype "passive"))
      (node (ref "R29") (pin "1") (pinfunction "1_1") (pintype "passive"))
      (node (ref "R35") (pin "1") (pinfunction "1_1") (pintype "passive"))
    )
    (net (code "57") (name "Net-(Q6-B)") (class "Default")
      (node (ref "Q6") (pin "1") (pinfunction "B_1") (pintype "passive"))
      (node (ref "R32") (pin "1") (pinfunction "1_1") (pintype "passive"))
      (node (ref "R36") (pin "1") (pinfunction "1_1") (pintype "passive"))
    )
    (net (code "58") (name "Net-(Q6-C)") (class "Default")
      (node (ref "LED1") (pin "4") (pinfunction "-_4") (pintype "passive"))
      (node (ref "Q6") (pin "3") (pinfunction "C_3") (pintype "passive"))
    )
    (net (code "59") (name "Net-(Q7-B)") (class "Default")
      (node (ref "Q7") (pin "1") (pinfunction "B_1") (pintype "passive"))
      (node (ref "R33") (pin "1") (pinfunction "1_1") (pintype "passive"))
      (node (ref "R37") (pin "1") (pinfunction "1_1") (pintype "passive"))
    )
    (net (code "60") (name "Net-(Q7-C)") (class "Default")
      (node (ref "LED1") (pin "5") (pinfunction "-_5") (pintype "passive"))
      (node (ref "Q7") (pin "3") (pinfunction "C_3") (pintype "passive"))
    )
    (net (code "61") (name "Net-(Q8-B)") (class "Default")
      (node (ref "Q8") (pin "1") (pinfunction "B_1") (pintype "passive"))
      (node (ref "R34") (pin "1") (pinfunction "1_1") (pintype "passive"))
      (node (ref "R38") (pin "1") (pinfunction "1_1") (pintype "passive"))
    )
    (net (code "62") (name "Net-(Q8-C)") (class "Default")
      (node (ref "LED1") (pin "6") (pinfunction "-_6") (pintype "passive"))
      (node (ref "Q8") (pin "3") (pinfunction "C_3") (pintype "passive"))
    )
    (net (code "63") (name "Net-(Q9-G1)") (class "Default")
      (node (ref "C20") (pin "2") (pinfunction "2_2") (pintype "passive"))
      (node (ref "Q9") (pin "1") (pinfunction "G1_1") (pintype "passive"))
      (node (ref "R39") (pin "1") (pinfunction "1_1") (pintype "passive"))
      (node (ref "R40") (pin "1") (pinfunction "1_1") (pintype "passive"))
    )
    (net (code "64") (name "Net-(Q9-G2)") (class "Default")
      (node (ref "C21") (pin "2") (pinfunction "2_2") (pintype "passive"))
      (node (ref "Q9") (pin "8") (pinfunction "G2_8") (pintype "passive"))
      (node (ref "R41") (pin "1") (pinfunction "1_1") (pintype "passive"))
      (node (ref "R42") (pin "1") (pinfunction "1_1") (pintype "passive"))
    )
    (net (code "65") (name "Net-(R5-Pad2)") (class "Default")
      (node (ref "R5") (pin "2") (pinfunction "2_2") (pintype "passive"))
      (node (ref "R9") (pin "1") (pinfunction "1_1") (pintype "passive"))
    )
    (net (code "66") (name "Net-(U1-FB)") (class "Default")
      (node (ref "C7") (pin "1") (pinfunction "1_1") (pintype "passive"))
      (node (ref "R2") (pin "2") (pinfunction "2_2") (pintype "passive"))
      (node (ref "R5") (pin "1") (pinfunction "1_1") (pintype "passive"))
      (node (ref "U1") (pin "3") (pinfunction "FB_3") (pintype "passive"))
    )
    (net (code "67") (name "Net-(U1-GVDD)") (class "Default")
      (node (ref "C1") (pin "2") (pinfunction "2_2") (pintype "passive"))
      (node (ref "U1") (pin "1") (pinfunction "GVDD_1") (pintype "passive"))
    )
    (net (code "68") (name "Net-(U1-LX)") (class "Default")
      (node (ref "L1") (pin "1") (pinfunction "1_1") (pintype "passive"))
      (node (ref "U1") (pin "6") (pinfunction "LX_6") (pintype "passive"))
    )
    (net (code "69") (name "Net-(U2-ICHG)") (class "Default")
      (node (ref "R3") (pin "1") (pinfunction "1_1") (pintype "passive"))
      (node (ref "U2") (pin "6") (pinfunction "ICHG_6") (pintype "passive"))
    )
    (net (code "70") (name "Net-(U2-NTC)") (class "Default")
      (node (ref "R11") (pin "1") (pinfunction "1_1") (pintype "passive"))
      (node (ref "R7") (pin "2") (pinfunction "2_2") (pintype "passive"))
      (node (ref "U2") (pin "7") (pinfunction "NTC_7") (pintype "passive"))
    )
    (net (code "71") (name "Net-(U4-AVDD)") (class "Default")
      (node (ref "C29") (pin "2") (pinfunction "2_2") (pintype "passive"))
      (node (ref "U4") (pin "3") (pinfunction "AVDD_3") (pintype "passive"))
    )
    (net (code "72") (name "Net-(U4-P0.2{slash}RSTN)") (class "Default")
      (node (ref "C28") (pin "1") (pinfunction "1_1") (pintype "passive"))
      (node (ref "U4") (pin "2") (pinfunction "P0.2/RSTN_2") (pintype "passive"))
    )
    (net (code "73") (name "VBAT_8V4") (class "Default")
      (node (ref "C14") (pin "2") (pinfunction "2_2") (pintype "passive"))
      (node (ref "C15") (pin "2") (pinfunction "2_2") (pintype "passive"))
      (node (ref "C6") (pin "2") (pinfunction "2_2") (pintype "passive"))
      (node (ref "DS1") (pin "1") (pinfunction "A_1") (pintype "passive"))
      (node (ref "P1") (pin "1") (pinfunction "1_1") (pintype "passive"))
      (node (ref "R13") (pin "1") (pinfunction "1_1") (pintype "passive"))
      (node (ref "R44") (pin "1") (pinfunction "1_1") (pintype "passive"))
      (node (ref "R8") (pin "2") (pinfunction "2_2") (pintype "passive"))
      (node (ref "U1") (pin "5") (pinfunction "VIN_5") (pintype "passive"))
      (node (ref "U2") (pin "5") (pinfunction "BAT_5") (pintype "passive"))
    )
    (net (code "74") (name "VDD") (class "Default")
      (node (ref "Q1") (pin "2") (pinfunction "D1_2") (pintype "passive"))
      (node (ref "Q1") (pin "3") (pinfunction "D1_3") (pintype "passive"))
      (node (ref "Q1") (pin "4") (pinfunction "D1_4") (pintype "passive"))
      (node (ref "Q1") (pin "9") (pinfunction "D1_9") (pintype "passive"))
      (node (ref "Q2") (pin "2") (pinfunction "D1_2") (pintype "passive"))
      (node (ref "Q2") (pin "3") (pinfunction "D1_3") (pintype "passive"))
      (node (ref "Q2") (pin "4") (pinfunction "D1_4") (pintype "passive"))
      (node (ref "Q2") (pin "9") (pinfunction "D1_9") (pintype "passive"))
      (node (ref "Q9") (pin "2") (pinfunction "D1_2") (pintype "passive"))
      (node (ref "Q9") (pin "3") (pinfunction "D1_3") (pintype "passive"))
      (node (ref "Q9") (pin "4") (pinfunction "D1_4") (pintype "passive"))
      (node (ref "Q9") (pin "9") (pinfunction "D1_9") (pintype "passive"))
      (node (ref "U4") (pin "27") (pinfunction "VCC_27") (pintype "passive"))
    )
    (net (code "75") (name "unconnected-(U4-GND-Pad0)") (class "Default")
      (node (ref "U4") (pin "0") (pinfunction "GND_0") (pintype "passive"))
    )
    (net (code "76") (name "unconnected-(U4-GND-Pad17)") (class "Default")
      (node (ref "U4") (pin "17") (pinfunction "GND_17") (pintype "passive+no_connect"))
    )
    (net (code "77") (name "unconnected-(U4-MCPWM_CH4N{slash}OPA2_IN{slash}P3.11-Pad32)") (class "Default")
      (node (ref "U4") (pin "32") (pinfunction "MCPWM_CH4N/OPA2_IN/P3.11_32") (pintype "passive+no_connect"))
    )
    (net (code "78") (name "unconnected-(U4-MCPWM_CH4P{slash}OPA2_IP{slash}P3.10-Pad31)") (class "Default")
      (node (ref "U4") (pin "31") (pinfunction "MCPWM_CH4P/OPA2_IP/P3.10_31") (pintype "passive+no_connect"))
    )
    (net (code "79") (name "unconnected-(U4-MCPWM_CH5N{slash}SPI_DO{slash}SDA{slash}P2.10-Pad34)") (class "Default")
      (node (ref "U4") (pin "34") (pinfunction "MCPWM_CH5N/SPI_DO/SDA/P2.10_34") (pintype "passive+no_connect"))
    )
    (net (code "80") (name "unconnected-(U4-OPA3_IN{slash}P3.14-Pad35)") (class "Default")
      (node (ref "U4") (pin "35") (pinfunction "OPA3_IN/P3.14_35") (pintype "passive+no_connect"))
    )
    (net (code "81") (name "unconnected-(U4-P0.15{slash}CMP2_OUT{slash}MCPWM_CH0P{slash}UART0_RXD{slash}SPI_DO{slash}SDA{slash}TIM0_CH0{slash}CMP0_IN-Pad12)") (class "Default")
      (node (ref "U4") (pin "12") (pinfunction "P0.15/CMP2_OUT/MCPWM_CH0P/UART0_RXD/SPI_DO/SDA/TIM0_CH0/CMP0_IN_12") (pintype "passive+no_connect"))
    )
    (net (code "82") (name "unconnected-(U4-P1.0{slash}MCPWM_CH0N{slash}UART0_TXD{slash}SPI_DI-Pad13)") (class "Default")
      (node (ref "U4") (pin "13") (pinfunction "P1.0/MCPWM_CH0N/UART0_TXD/SPI_DI_13") (pintype "passive+no_connect"))
    )
    (net (code "83") (name "unconnected-(U4-P2.7{slash}UART0_TXD{slash}TIM0_CH0{slash}TIM3_CH1{slash}CLUOUT1{slash}ADC0_CH11{slash}OPAx_OUT{slash}LDO15{slash}REF-Pad16)") (class "Default")
      (node (ref "U4") (pin "16") (pinfunction "P2.7/UART0_TXD/TIM0_CH0/TIM3_CH1/CLUOUT1/ADC0_CH11/OPAx_OUT/LDO15/REF_16") (pintype "passive+no_connect"))
    )
  )
)
